# Full_Schematic.net
KiCad netlist of a schematic drawn in Altium Designer
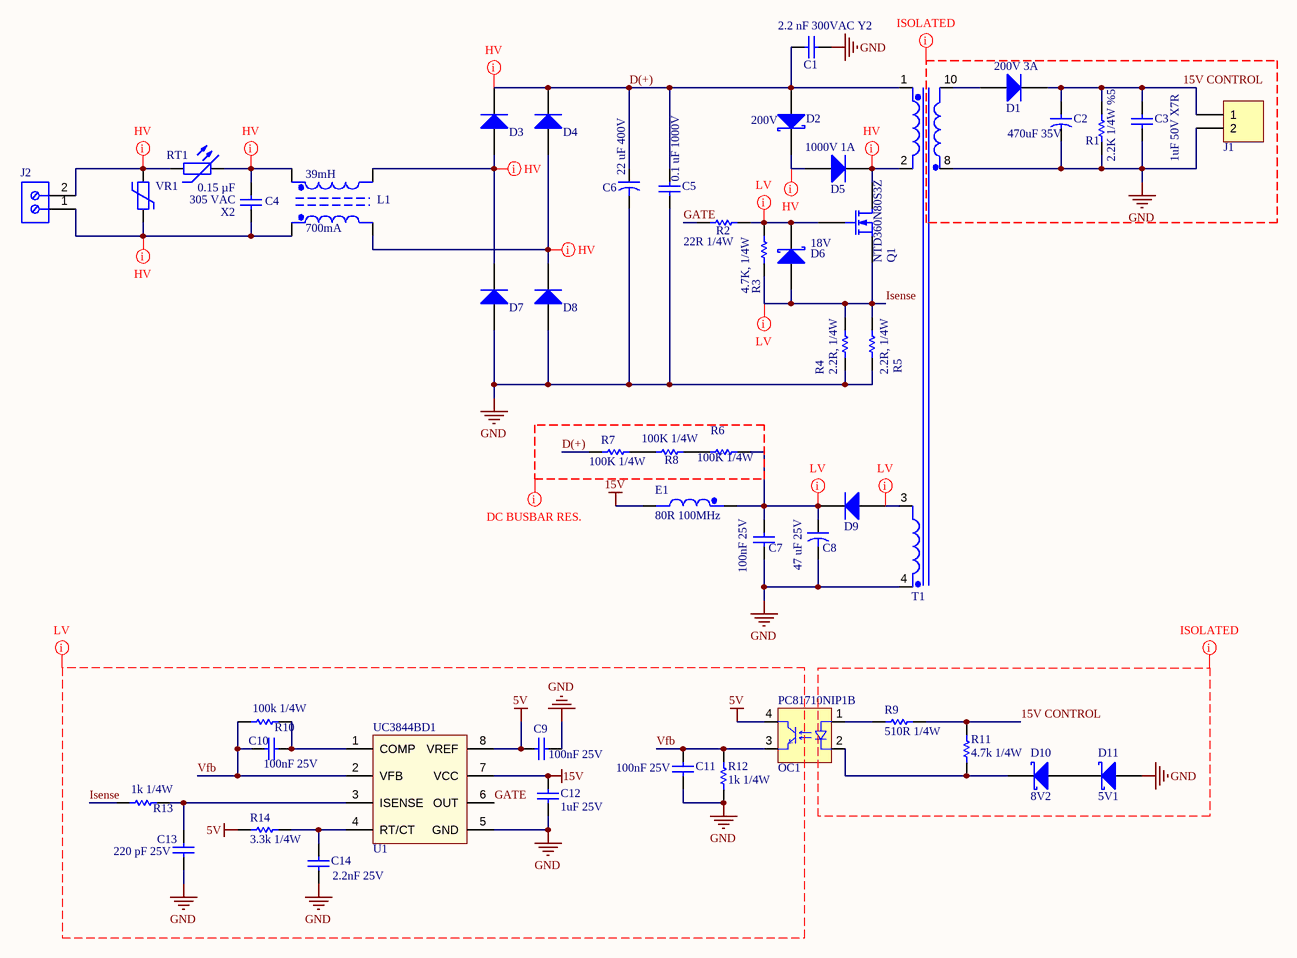
[diagram p0: Full_Schematic.SchDoc]

(export (version "E")
  (design (tool "Eeschema 10.0.6"))
  (components
    (comp (ref "C1")
      (value "2.2 nF 300VAC Y2")
      (footprint "4x13x9")
      (description "Film Capacitor, Polypropylene, 1500V, 20% +Tol, 20% -Tol, 0.0022uF, Through Hole Mount")
      (fields
        (field (name "MANUFACTURER") "TDK EPCOS")
        (field (name "MANUFACTURER PART NUMBER") "B32021A3222M189")
        (field (name "PUBLISHER") "Altium Limited")
        (field (name "DESIGNED BY") "Ahmet Can")
      )
      (libsource (lib "FlybackKutuphane") (part "Cap Y2 2.2nF 300V MKP TDK"))
    )
    (comp (ref "C2")
      (value "470uF 35V")
      (footprint "CAPPRD500W60D1025H1750")
      (description "Cap Aluminum 470uF 35V 20% (10 X 16mm) Radial 5mm 1760mA 10000h 105 C Bulk")
      (fields
        (field (name "MANUFACTURER") "Rubycon")
        (field (name "MANUFACTURER PART NUMBER") "35ZLH470MEFC10X16")
        (field (name "DESIGNED BY") "Ahmet Can")
      )
      (libsource (lib "FlybackKutuphane") (part "C 470uF 35V 1.76A 28mOhm"))
    )
    (comp (ref "C3")
      (value "1uF 50V X7R")
      (footprint "1206")
      (description "SMD 1206")
      (libsource (lib "") (part "C 1206_1"))
    )
    (comp (ref "C4")
      (value "0.15 µF")
      (footprint "CFR F15 L18 B6 H12")
      (description "MPX Boxed Metalized Propylene X2 Class Interference Suppressor Film Capacitors")
      (fields
        (field (name "MANUFACTURER") "Cornell Dubilier")
        (field (name "MANUFACTURER PART NUMBER") "MPX154K305E")
        (field (name "RATINGS") "X2")
        (field (name "VOLTAGE RATING - AC") "305 VAC")
        (field (name "DESIGNED BY") "Ahmet Can")
      )
      (libsource (lib "FlybackKutuphane") (part "Cap 150nF 305VAC X2"))
    )
    (comp (ref "C5")
      (value "0.1 uF 1000V")
      (footprint "RCE7U2J333J5B1H03B")
      (description "Cap Ceramic 0.1uF 1000V X7R 10% Radial 5mm 125°C Bulk")
      (fields
        (field (name "MANUFACTURER") "Murata")
        (field (name "MANUFACTURER PART NUMBER") "RDER73A104K5B1H03B")
        (field (name "PUBLISHER") "Altium Limited")
      )
      (libsource (lib "FlybackKutuphane") (part "C Seramik 100nF 1kV X7R 5mm"))
    )
    (comp (ref "C6")
      (value "22 uF 400V")
      (footprint "22uF 400V")
      (description "Cap Aluminum Lytic 22uF 400V 20%( 12.5 X 16mm) Radial 5mm 180mA 2000h 105C")
      (fields
        (field (name "MANUFACTURER") "Rubycon")
        (field (name "MANUFACTURER PART NUMBER") "400AX22MEFC12.5X16")
        (field (name "DESIGNED BY") "Ahmet Can")
      )
      (libsource (lib "FlybackKutuphane") (part "C 22uF 400V 270mArms"))
    )
    (comp (ref "C7")
      (value "100nF 25V")
      (footprint "1206")
      (description "SMD 1206")
      (libsource (lib "") (part "C 1206_1"))
    )
    (comp (ref "C8")
      (value "47 uF 25V")
      (footprint "CAPPRD200W50D525H1250")
      (fields
        (field (name "MANUFACTURER") "Rubycon")
        (field (name "MANUFACTURER PART NUMBER") "25YXJ47MTA5X11")
        (field (name "TOLERANCE") "20%")
        (field (name "DESIGNED BY") "Ahmet Can")
      )
      (libsource (lib "FlybackKutuphane") (part "C 47uF 25V 250mArms 400mOhm"))
    )
    (comp (ref "C9")
      (value "100nF 25V")
      (footprint "R 1206")
      (description "SMD 1206")
      (libsource (lib "FlybackKutuphane") (part "C 1206"))
    )
    (comp (ref "C10")
      (value "100nF 25V")
      (footprint "1206")
      (description "SMD 1206")
      (libsource (lib "FlybackKutuphane") (part "C 1206"))
    )
    (comp (ref "C11")
      (value "100nF 25V")
      (footprint "1206")
      (description "SMD 1206")
      (libsource (lib "FlybackKutuphane") (part "C 1206"))
    )
    (comp (ref "C12")
      (value "1uF 25V")
      (footprint "R 1206")
      (description "SMD 1206")
      (libsource (lib "FlybackKutuphane") (part "C 1206"))
    )
    (comp (ref "C13")
      (value "220 pF 25V")
      (footprint "1206")
      (description "SMD 1206")
      (libsource (lib "FlybackKutuphane") (part "C 1206"))
    )
    (comp (ref "C14")
      (value "2.2nF 25V")
      (footprint "1206")
      (description "SMD 1206")
      (libsource (lib "FlybackKutuphane") (part "C 1206"))
    )
    (comp (ref "D1")
      (value "200V 3A")
      (footprint "DO-201AD -Dik")
      (description "Diode Schottky 200V 3A DO201AD")
      (fields
        (field (name "MANUFACTURER") "Sangdest Microelectronics")
        (field (name "MANUFACTURER PART NUMBER") "SB3200")
        (field (name "DESIGNED BY") "Ahmet Can")
      )
      (libsource (lib "FlybackKutuphane") (part "Diyot DO-201AD Dik"))
    )
    (comp (ref "D2")
      (value "200V")
      (footprint "DO-15((DO-204AC)")
      (description "Diode Transient Voltage Suppression (TVS) Single Unidirectional 171 Volt 600 Watt 2-Pin DO-15")
      (fields
        (field (name "MANUFACTURER") "STMicroelectronics")
        (field (name "MANUFACTURER PART NUMBER") "P6KE200A")
        (field (name "DESIGNED BY") "Ahmet Can")
      )
      (libsource (lib "FlybackKutuphane") (part "TVS 200V DO-15"))
    )
    (comp (ref "D3")
      (value "1N4007FLTR")
      (footprint "DO-214AA(SMB)")
      (description "Standard Rectifier 1000V SOD-123")
      (fields (field (name "DESIGNED BY") "Ahmet Can"))
      (libsource (lib "FlybackKutuphane") (part "D 1N4007 DO-214AA(SMB)"))
    )
    (comp (ref "D4")
      (value "1N4007FLTR")
      (footprint "DO-214AA(SMB)")
      (description "Standard Rectifier 1000V SOD-123")
      (fields (field (name "DESIGNED BY") "Ahmet Can"))
      (libsource (lib "FlybackKutuphane") (part "D 1N4007 DO-214AA(SMB)"))
    )
    (comp (ref "D5")
      (value "1000V 1A")
      (footprint "DO-214AA(SMB)")
      (description "Standard Rectifier 1000V SOD-123, 1N4007FLTR")
      (fields (field (name "DESIGNED BY") "Ahmet Can"))
      (libsource (lib "FlybackKutuphane") (part "D 1N4007 DO-214AA(SMB)"))
    )
    (comp (ref "D6")
      (value "18V")
      (footprint "SOD-123")
      (description "SOD-123")
      (fields (field (name "PUBLISHER") "Altium Limited"))
      (libsource (lib "FlybackKutuphane") (part "Zener SOD-123"))
    )
    (comp (ref "D7")
      (value "1N4007FLTR")
      (footprint "DO-214AA(SMB)")
      (description "Standard Rectifier 1000V SOD-123")
      (fields (field (name "DESIGNED BY") "Ahmet Can"))
      (libsource (lib "FlybackKutuphane") (part "D 1N4007 DO-214AA(SMB)"))
    )
    (comp (ref "D8")
      (value "1N4007FLTR")
      (footprint "DO-214AA(SMB)")
      (description "Standard Rectifier 1000V SOD-123")
      (fields (field (name "DESIGNED BY") "Ahmet Can"))
      (libsource (lib "FlybackKutuphane") (part "D 1N4007 DO-214AA(SMB)"))
    )
    (comp (ref "D9")
      (value "ES2D")
      (footprint "DO-214AA(SMB)")
      (description "Superfast Recovery Rectifier , DO-214AA/SMB, 200V, 2.00A, 20ns")
      (fields
        (field (name "MANUFACTURER") "ON Semiconductor / Fairchild")
        (field (name "DESIGNED BY") "Ahmet Can")
      )
      (libsource (lib "FlybackKutuphane") (part "D ES2D"))
    )
    (comp (ref "D10")
      (value "8V2")
      (footprint "SOD-123")
      (description "SOD-123")
      (fields (field (name "PUBLISHER") "Altium Limited"))
      (libsource (lib "FlybackKutuphane") (part "Zener SOD-123"))
    )
    (comp (ref "D11")
      (value "5V1")
      (footprint "SOD-123")
      (description "SOD-123")
      (fields (field (name "PUBLISHER") "Altium Limited"))
      (libsource (lib "FlybackKutuphane") (part "Zener SOD-123"))
    )
    (comp (ref "E1")
      (value "80R 100MHz")
      (footprint "1206 Bead")
      (description "Ferrite Beads Multi-Layer 50Ohm 25% 100MHz 3A 25mOhm DCR 1206 T/R, 742792114")
      (fields
        (field (name "MANUFACTURER") "Wurth Electronics")
        (field (name "MANUFACTURER PART NUMBER") "742792114")
        (field (name "DESIGNED BY") "Ahmet Can")
      )
      (libsource (lib "FlybackKutuphane") (part "Ferrite Bead 1206"))
    )
    (comp (ref "J1")
      (value "691210910002")
      (footprint "Header 2pin 2.54mm Vidalı")
      (description "Tb, Wire To Brd, R/A, 2Way, 18Awg Rohs Compliant: Yes ¦Wurth Elektronik 691210910002")
      (fields
        (field (name "MANUFACTURER") "Wurth Electronics")
        (field (name "VOLTAGE") "150V")
        (field (name "PUBLISHER") "Altium Limited")
        (field (name "DESIGNED BY") "Ahmet Can")
      )
      (libsource (lib "FlybackKutuphane") (part "Header 2 Pin 2.54mm TH"))
    )
    (comp (ref "J2")
      (value "691214410002")
      (footprint "Header 2 Pin 7.62mm Vidalı")
      (description "7.62 Mm Terminal Block, Horizont")
      (fields
        (field (name "PART NUMBER") "691218410002")
        (field (name "MANUFACTURER") "Wurth Electronics")
        (field (name "PUBLISHER") "Wurth Elektronik")
        (field (name "DESIGNED BY") "Ahmet Can")
      )
      (libsource (lib "FlybackKutuphane") (part "Header 2pin 7.62mm TH"))
    )
    (comp (ref "L1")
      (value "39mH")
      (footprint "EMC SMPS TDK")
      (description "Common Mode Chokes Dual 39mH 10kHz 700mA Thru-Hole Box")
      (fields
        (field (name "MANUFACTURER") "TDK EPCOS")
        (field (name "MANUFACTURER PART NUMBER") "B82732R2701B030")
        (field (name "MAX CURRENT RATING") "700mA")
        (field (name "DESIGNED BY") "Ahmet Can")
      )
      (libsource (lib "FlybackKutuphane") (part "EMC SMPS TDK 39mH 0.7A"))
    )
    (comp (ref "OC1")
      (value "PC81710NIP1B")
      (footprint "PC817 SMD")
      (description "Optocoupler 1-CH Open Collector 5000Vrms 4-Pin DIP SMD T/R")
      (fields (field (name "MANUFACTURER") "Sharp") (field (name "DESIGNED BY") "Ahmet Can"))
      (libsource (lib "FlybackKutuphane") (part "PC817"))
    )
    (comp (ref "Q1")
      (value "NTD360N80S3Z")
      (footprint "DPAK IGBT")
      (description "MOSFET – Power, N-Channel, SUPERFET® III, 800 V, 13 A, 360 mΩ, DPAK")
      (fields (field (name "MANUFACTURER") "ON Semiconductor") (field (name "PUBLISHER") "Altium Limited"))
      (libsource (lib "FlybackKutuphane") (part "MOSFET DPAK"))
    )
    (comp (ref "R1")
      (value "2.2K 1/4W %5")
      (footprint "R 1206")
      (description "SMD 1206")
      (libsource (lib "FlybackKutuphane") (part "R 1206"))
    )
    (comp (ref "R2")
      (value "22R 1/4W")
      (footprint "R 1206")
      (description "SMD 1206")
      (libsource (lib "FlybackKutuphane") (part "R 1206"))
    )
    (comp (ref "R3")
      (value "4.7K, 1/4W")
      (footprint "R 1206")
      (description "SMD 1206")
      (libsource (lib "FlybackKutuphane") (part "R 1206"))
    )
    (comp (ref "R4")
      (value "2.2R, 1/4W")
      (footprint "R 1206")
      (description "SMD 1206")
      (libsource (lib "FlybackKutuphane") (part "R 1206"))
    )
    (comp (ref "R5")
      (value "2.2R, 1/4W")
      (footprint "R 1206")
      (description "SMD 1206")
      (libsource (lib "FlybackKutuphane") (part "R 1206"))
    )
    (comp (ref "R6")
      (value "100K 1/4W")
      (footprint "R 1206")
      (description "SMD 1206")
      (libsource (lib "FlybackKutuphane") (part "R 1206"))
    )
    (comp (ref "R7")
      (value "100K 1/4W")
      (footprint "R 1206")
      (description "SMD 1206")
      (libsource (lib "FlybackKutuphane") (part "R 1206"))
    )
    (comp (ref "R8")
      (value "100K 1/4W")
      (footprint "R 1206")
      (description "SMD 1206")
      (libsource (lib "FlybackKutuphane") (part "R 1206"))
    )
    (comp (ref "R9")
      (value "510R 1/4W")
      (footprint "R 1206")
      (description "SMD 1206")
      (libsource (lib "FlybackKutuphane") (part "R 1206"))
    )
    (comp (ref "R10")
      (value "100k 1/4W")
      (footprint "R 1206")
      (description "SMD 1206")
      (libsource (lib "FlybackKutuphane") (part "R 1206"))
    )
    (comp (ref "R11")
      (value "4.7k 1/4W")
      (footprint "R 1206")
      (description "SMD 1206")
      (libsource (lib "FlybackKutuphane") (part "R 1206"))
    )
    (comp (ref "R12")
      (value "1k 1/4W")
      (footprint "1206")
      (description "SMD 1206")
      (libsource (lib "FlybackKutuphane") (part "R 1206"))
    )
    (comp (ref "R13")
      (value "1k 1/4W")
      (footprint "R 1206")
      (description "SMD 1206")
      (libsource (lib "FlybackKutuphane") (part "R 1206"))
    )
    (comp (ref "R14")
      (value "3.3k 1/4W")
      (footprint "R 1206")
      (description "SMD 1206")
      (libsource (lib "FlybackKutuphane") (part "R 1206"))
    )
    (comp (ref "RT1")
      (value "NTC  B57153S0100M000")
      (footprint "NTC B57153S0100")
      (description "Inrush current limiters include PTC and NTC Thermistors.")
      (fields
        (field (name "MANUFACTURER") "TDK EPCOS")
        (field (name "MANUFACTURER PART NUMBER") "B57153S0100M000")
        (field (name "PUBLISHER") "Altium Limited")
        (field (name "DESIGNED BY") "Ahmet Can")
      )
      (libsource (lib "FlybackKutuphane") (part "NTC 10R 2A 8.5mm"))
    )
    (comp (ref "T1")
      (value "SMPS Tr")
      (footprint "SMPS Tr3")
      (fields (field (name "PUBLISHER") "Altium Limited"))
      (libsource (lib "FlybackKutuphane") (part "SMPS Tr EF25"))
    )
    (comp (ref "U1")
      (value "UC3844BD1")
      (footprint "SOIC-OA8_L")
      (description "Off-Line Controllers 52kHz 1A Current PWM No-Cancel/No-Return")
      (fields (field (name "MANUFACTURER") "STMicroelectronics"))
      (libsource (lib "FlybackKutuphane") (part "UC3844BD1"))
    )
    (comp (ref "VR1")
      (value "B72314P2301K101")
      (footprint "Varistor630V")
      (description "Varistor Metal Oxide 350pF 50A 470V Through Hole Bulk")
      (fields (field (name "MANUFACTURER") "TDK EPCOS") (field (name "DESIGNED BY") "Ahmet Can"))
      (libsource (lib "FlybackKutuphane") (part "Varistor V20E320P"))
    )
  )
  (nets
    (net (code "1") (name "/15V CONTROL") (class "Default")
      (node (ref "C2") (pin "1") (pinfunction "1_1") (pintype "passive"))
      (node (ref "C3") (pin "2") (pinfunction "2_2") (pintype "passive"))
      (node (ref "D1") (pin "2") (pinfunction "K_2") (pintype "passive"))
      (node (ref "J1") (pin "1") (pinfunction "1_1") (pintype "passive"))
      (node (ref "R1") (pin "2") (pinfunction "2_2") (pintype "passive"))
      (node (ref "R11") (pin "1") (pinfunction "1_1") (pintype "passive"))
      (node (ref "R9") (pin "1") (pinfunction "1_1") (pintype "passive"))
    )
    (net (code "2") (name "/D(+)") (class "Default")
      (node (ref "C1") (pin "1") (pinfunction "1_1") (pintype "passive"))
      (node (ref "C5") (pin "2") (pinfunction "2_2") (pintype "passive"))
      (node (ref "C6") (pin "1") (pinfunction "1_1") (pintype "passive"))
      (node (ref "D2") (pin "1") (pinfunction "A_1") (pintype "passive"))
      (node (ref "D3") (pin "2") (pinfunction "K_2") (pintype "passive"))
      (node (ref "D4") (pin "2") (pinfunction "K_2") (pintype "passive"))
      (node (ref "R7") (pin "1") (pinfunction "1_1") (pintype "passive"))
      (node (ref "T1") (pin "1") (pinfunction "Pri+_1") (pintype "passive"))
    )
    (net (code "3") (name "/GATE") (class "Default")
      (node (ref "R2") (pin "2") (pinfunction "2_2") (pintype "passive"))
      (node (ref "U1") (pin "6") (pinfunction "OUT_6") (pintype "power_in"))
    )
    (net (code "4") (name "/Isense") (class "Default")
      (node (ref "D6") (pin "1") (pinfunction "A_1") (pintype "passive"))
      (node (ref "Q1") (pin "3") (pinfunction "S_3") (pintype "passive"))
      (node (ref "R13") (pin "1") (pinfunction "1_1") (pintype "passive"))
      (node (ref "R3") (pin "1") (pinfunction "1_1") (pintype "passive"))
      (node (ref "R4") (pin "2") (pinfunction "2_2") (pintype "passive"))
      (node (ref "R5") (pin "2") (pinfunction "2_2") (pintype "passive"))
    )
    (net (code "5") (name "/Vfb") (class "Default")
      (node (ref "C10") (pin "1") (pinfunction "1_1") (pintype "passive"))
      (node (ref "C11") (pin "2") (pinfunction "2_2") (pintype "passive"))
      (node (ref "OC1") (pin "3") (pinfunction "E_3") (pintype "passive"))
      (node (ref "R10") (pin "1") (pinfunction "1_1") (pintype "passive"))
      (node (ref "R12") (pin "2") (pinfunction "2_2") (pintype "passive"))
      (node (ref "U1") (pin "2") (pinfunction "VFB_2") (pintype "passive"))
    )
    (net (code "6") (name "5V") (class "Default")
      (node (ref "C9") (pin "1") (pinfunction "1_1") (pintype "passive"))
      (node (ref "OC1") (pin "4") (pinfunction "C_4") (pintype "passive"))
      (node (ref "R14") (pin "1") (pinfunction "1_1") (pintype "passive"))
      (node (ref "U1") (pin "8") (pinfunction "VREF_8") (pintype "passive"))
    )
    (net (code "7") (name "15V") (class "Default")
      (node (ref "C12") (pin "2") (pinfunction "2_2") (pintype "passive"))
      (node (ref "E1") (pin "2") (pinfunction "2_2") (pintype "passive"))
      (node (ref "U1") (pin "7") (pinfunction "VCC_7") (pintype "passive"))
    )
    (net (code "8") (name "GND") (class "Default")
      (node (ref "C1") (pin "2") (pinfunction "2_2") (pintype "passive"))
      (node (ref "C11") (pin "1") (pinfunction "1_1") (pintype "passive"))
      (node (ref "C12") (pin "1") (pinfunction "1_1") (pintype "passive"))
      (node (ref "C13") (pin "1") (pinfunction "1_1") (pintype "passive"))
      (node (ref "C14") (pin "1") (pinfunction "1_1") (pintype "passive"))
      (node (ref "C2") (pin "2") (pinfunction "2_2") (pintype "passive"))
      (node (ref "C3") (pin "1") (pinfunction "1_1") (pintype "passive"))
      (node (ref "C5") (pin "1") (pinfunction "1_1") (pintype "passive"))
      (node (ref "C6") (pin "2") (pinfunction "2_2") (pintype "passive"))
      (node (ref "C7") (pin "1") (pinfunction "1_1") (pintype "passive"))
      (node (ref "C8") (pin "2") (pinfunction "2_2") (pintype "passive"))
      (node (ref "C9") (pin "2") (pinfunction "2_2") (pintype "passive"))
      (node (ref "D11") (pin "1") (pinfunction "A_1") (pintype "passive"))
      (node (ref "D7") (pin "1") (pinfunction "A_1") (pintype "passive"))
      (node (ref "D8") (pin "1") (pinfunction "A_1") (pintype "passive"))
      (node (ref "J1") (pin "2") (pinfunction "2_2") (pintype "passive"))
      (node (ref "R1") (pin "1") (pinfunction "1_1") (pintype "passive"))
      (node (ref "R12") (pin "1") (pinfunction "1_1") (pintype "passive"))
      (node (ref "R4") (pin "1") (pinfunction "1_1") (pintype "passive"))
      (node (ref "R5") (pin "1") (pinfunction "1_1") (pintype "passive"))
      (node (ref "T1") (pin "4") (pinfunction "Sec3-_4") (pintype "passive"))
      (node (ref "T1") (pin "8") (pinfunction "8_8") (pintype "passive"))
      (node (ref "U1") (pin "5") (pinfunction "GND_5") (pintype "power_in"))
    )
    (net (code "9") (name "Net-(C4-Pad1)") (class "Default")
      (node (ref "C4") (pin "1") (pinfunction "1_1") (pintype "passive"))
      (node (ref "J2") (pin "1") (pinfunction "1_1") (pintype "passive"))
      (node (ref "L1") (pin "1") (pinfunction "1_1") (pintype "passive"))
      (node (ref "VR1") (pin "1") (pinfunction "1_1") (pintype "passive"))
    )
    (net (code "10") (name "Net-(C4-Pad2)") (class "Default")
      (node (ref "C4") (pin "2") (pinfunction "2_2") (pintype "passive"))
      (node (ref "L1") (pin "2") (pinfunction "2_2") (pintype "passive"))
      (node (ref "RT1") (pin "2") (pinfunction "2_2") (pintype "passive"))
    )
    (net (code "11") (name "Net-(D1-A)") (class "Default")
      (node (ref "D1") (pin "1") (pinfunction "A_1") (pintype "passive"))
      (node (ref "T1") (pin "10") (pinfunction "Sec1+_10") (pintype "passive"))
    )
    (net (code "12") (name "Net-(D2-K)") (class "Default")
      (node (ref "D2") (pin "2") (pinfunction "K_2") (pintype "passive"))
      (node (ref "D5") (pin "1") (pinfunction "A_1") (pintype "passive"))
    )
    (net (code "13") (name "Net-(D3-A)") (class "Default")
      (node (ref "D3") (pin "1") (pinfunction "A_1") (pintype "passive"))
      (node (ref "D7") (pin "2") (pinfunction "K_2") (pintype "passive"))
      (node (ref "L1") (pin "3") (pinfunction "3_3") (pintype "passive"))
    )
    (net (code "14") (name "Net-(D4-A)") (class "Default")
      (node (ref "D4") (pin "1") (pinfunction "A_1") (pintype "passive"))
      (node (ref "D8") (pin "2") (pinfunction "K_2") (pintype "passive"))
      (node (ref "L1") (pin "4") (pinfunction "4_4") (pintype "passive"))
    )
    (net (code "15") (name "Net-(D5-K)") (class "Default")
      (node (ref "D5") (pin "2") (pinfunction "K_2") (pintype "passive"))
      (node (ref "Q1") (pin "2") (pinfunction "D_2") (pintype "passive"))
      (node (ref "T1") (pin "2") (pinfunction "Pri-_2") (pintype "passive"))
    )
    (net (code "16") (name "Net-(D6-K)") (class "Default")
      (node (ref "D6") (pin "2") (pinfunction "K_2") (pintype "passive"))
      (node (ref "Q1") (pin "1") (pinfunction "G_1") (pintype "passive"))
      (node (ref "R2") (pin "1") (pinfunction "1_1") (pintype "passive"))
      (node (ref "R3") (pin "2") (pinfunction "2_2") (pintype "passive"))
    )
    (net (code "17") (name "Net-(D9-A)") (class "Default")
      (node (ref "D9") (pin "1") (pinfunction "A_1") (pintype "passive"))
      (node (ref "T1") (pin "3") (pinfunction "Sec3+_3") (pintype "passive"))
    )
    (net (code "18") (name "Net-(D9-K)") (class "Default")
      (node (ref "C7") (pin "2") (pinfunction "2_2") (pintype "passive"))
      (node (ref "C8") (pin "1") (pinfunction "1_1") (pintype "passive"))
      (node (ref "D9") (pin "2") (pinfunction "K_2") (pintype "passive"))
      (node (ref "E1") (pin "1") (pinfunction "1_1") (pintype "passive"))
      (node (ref "R6") (pin "2") (pinfunction "2_2") (pintype "passive"))
    )
    (net (code "19") (name "Net-(D10-A)") (class "Default")
      (node (ref "D10") (pin "1") (pinfunction "A_1") (pintype "passive"))
      (node (ref "D11") (pin "2") (pinfunction "K_2") (pintype "passive"))
    )
    (net (code "20") (name "Net-(D10-K)") (class "Default")
      (node (ref "D10") (pin "2") (pinfunction "K_2") (pintype "passive"))
      (node (ref "OC1") (pin "2") (pinfunction "K_2") (pintype "passive"))
      (node (ref "R11") (pin "2") (pinfunction "2_2") (pintype "passive"))
    )
    (net (code "21") (name "Net-(J2-Pad2)") (class "Default")
      (node (ref "J2") (pin "2") (pinfunction "2_2") (pintype "passive"))
      (node (ref "RT1") (pin "1") (pinfunction "1_1") (pintype "passive"))
      (node (ref "VR1") (pin "2") (pinfunction "2_2") (pintype "passive"))
    )
    (net (code "22") (name "Net-(OC1-A)") (class "Default")
      (node (ref "OC1") (pin "1") (pinfunction "A_1") (pintype "passive"))
      (node (ref "R9") (pin "2") (pinfunction "2_2") (pintype "passive"))
    )
    (net (code "23") (name "Net-(R6-Pad1)") (class "Default")
      (node (ref "R6") (pin "1") (pinfunction "1_1") (pintype "passive"))
      (node (ref "R8") (pin "2") (pinfunction "2_2") (pintype "passive"))
    )
    (net (code "24") (name "Net-(R7-Pad2)") (class "Default")
      (node (ref "R7") (pin "2") (pinfunction "2_2") (pintype "passive"))
      (node (ref "R8") (pin "1") (pinfunction "1_1") (pintype "passive"))
    )
    (net (code "25") (name "Net-(U1-COMP)") (class "Default")
      (node (ref "C10") (pin "2") (pinfunction "2_2") (pintype "passive"))
      (node (ref "R10") (pin "2") (pinfunction "2_2") (pintype "passive"))
      (node (ref "U1") (pin "1") (pinfunction "COMP_1") (pintype "power_in"))
    )
    (net (code "26") (name "Net-(U1-ISENSE)") (class "Default")
      (node (ref "C13") (pin "2") (pinfunction "2_2") (pintype "passive"))
      (node (ref "R13") (pin "2") (pinfunction "2_2") (pintype "passive"))
      (node (ref "U1") (pin "3") (pinfunction "ISENSE_3") (pintype "passive"))
    )
    (net (code "27") (name "Net-(U1-RT{slash}CT)") (class "Default")
      (node (ref "C14") (pin "2") (pinfunction "2_2") (pintype "passive"))
      (node (ref "R14") (pin "2") (pinfunction "2_2") (pintype "passive"))
      (node (ref "U1") (pin "4") (pinfunction "RT/CT_4") (pintype "power_in"))
    )
  )
)
